# short-cal-board-1point2in.net
KiCad netlist of a schematic drawn in Altium Designer
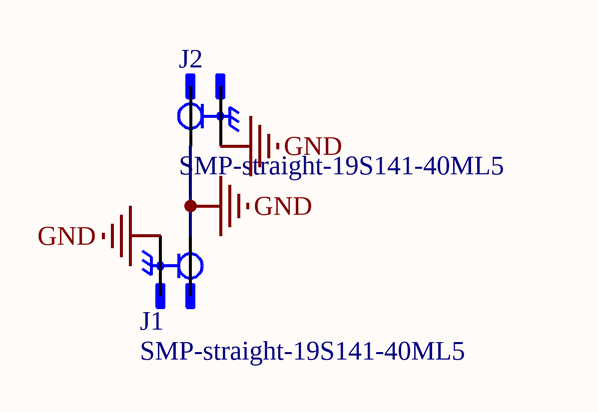
[diagram p0: short-cal-board-1point2in.SchDoc]

(export (version "E")
  (design (tool "Eeschema 10.0.6"))
  (components
    (comp (ref "J1")
      (value "SMP-straight-19S141-40ML5")
      (footprint "rosenberger-19S141-40ML5")
      (description "SMP Connector Plug, Male Pin 50Ohm Surface Mount Solder")
      (fields (field (name "MP") "853050232") (field (name "MF") "Molex"))
      (libsource (lib "") (part "SMP-straight-19S141-40ML5_1"))
    )
    (comp (ref "J2")
      (value "SMP-straight-19S141-40ML5")
      (footprint "rosenberger-19S141-40ML5")
      (description "SMP Connector Plug, Male Pin 50Ohm Surface Mount Solder")
      (fields (field (name "MP") "853050232") (field (name "MF") "Molex"))
      (libsource (lib "SchlibLafe") (part "SMP-straight-19S141-40ML5"))
    )
  )
  (nets
    (net (code "1") (name "GND") (class "Default")
      (node (ref "J1") (pin "1") (pinfunction "1_1") (pintype "passive"))
      (node (ref "J1") (pin "gnd") (pinfunction "gnd_gnd") (pintype "passive"))
      (node (ref "J2") (pin "1") (pinfunction "1_1") (pintype "passive"))
      (node (ref "J2") (pin "gnd") (pinfunction "gnd_gnd") (pintype "passive"))
    )
  )
)
